# SCH.net
KiCad netlist of a schematic drawn in EasyEDA
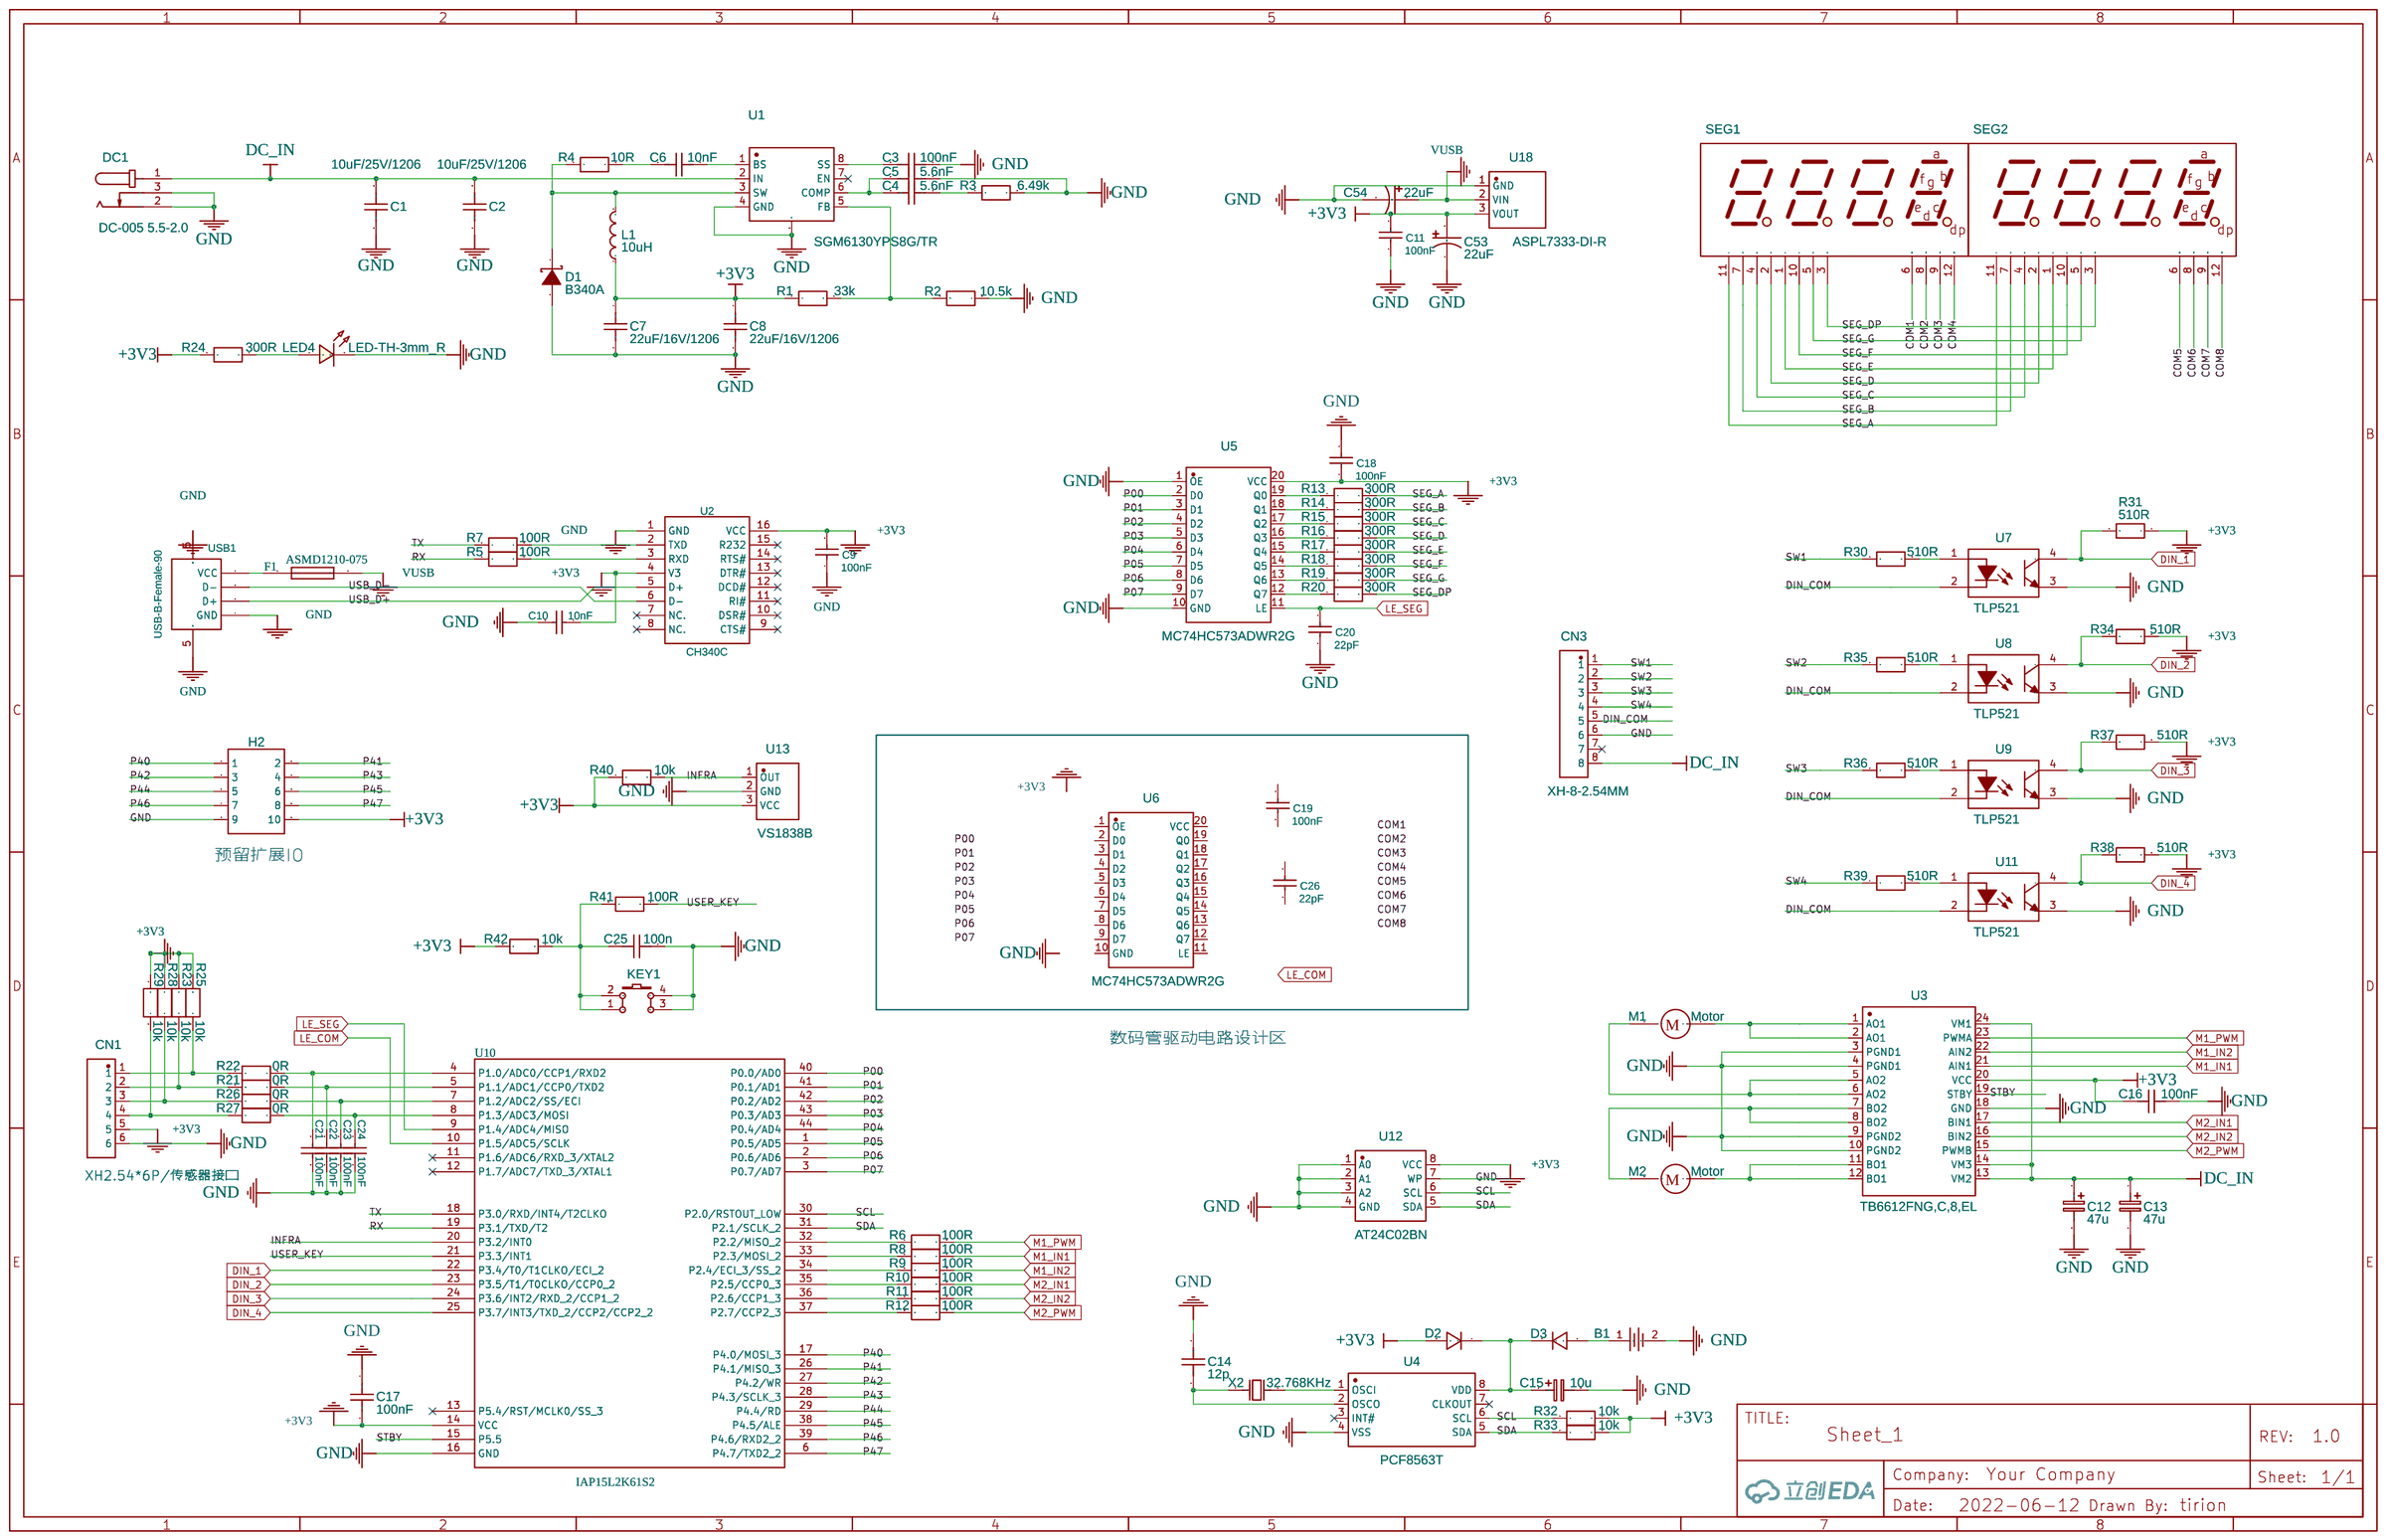
[diagram p0: schematic sheet]

(export (version "E")
  (design (tool "Eeschema 10.0.6"))
  (components
    (comp (ref "B1")
      (value "CR1220-2")
      (fields (field (name "BOM_Supplier Part") "C70381"))
      (libsource (lib "") (part "CR1220-2"))
    )
    (comp (ref "C1") (value "10uF/25V/1206") (libsource (lib "") (part "C_1206_US")))
    (comp (ref "C2") (value "10uF/25V/1206") (libsource (lib "") (part "C_1206_US")))
    (comp (ref "C3") (value "100nF") (libsource (lib "") (part "C_0805_US")))
    (comp (ref "C4") (value "5.6nF") (libsource (lib "") (part "C_0805_US")))
    (comp (ref "C5") (value "5.6nF") (libsource (lib "") (part "C_0805_US")))
    (comp (ref "C6") (value "10nF") (libsource (lib "") (part "C_0805_US")))
    (comp (ref "C7") (value "22uF/16V/1206") (libsource (lib "") (part "C_0805_US_2")))
    (comp (ref "C8") (value "22uF/16V/1206") (libsource (lib "") (part "C_0805_US_2")))
    (comp (ref "C9")
      (value "100nF")
      (fields
        (field (name "BOM_Manufacturer Part") "0805F104M500NT")
        (field (name "BOM_Supplier Part") "C28378")
      )
      (libsource (lib "") (part "0805F104M500NT_1"))
    )
    (comp (ref "C10")
      (value "10nF")
      (fields
        (field (name "BOM_Manufacturer Part") "0805F104M500NT")
        (field (name "BOM_Supplier Part") "C28378")
      )
      (libsource (lib "") (part "0805F104M500NT_2"))
    )
    (comp (ref "C11")
      (value "100nF")
      (fields
        (field (name "BOM_Manufacturer Part") "0805F104M500NT")
        (field (name "BOM_Supplier Part") "C28378")
      )
      (libsource (lib "") (part "0805F104M500NT_1"))
    )
    (comp (ref "C12") (value "47u") (libsource (lib "") (part "CE_SMD_D6.3×H5.5_EU")))
    (comp (ref "C13") (value "47u") (libsource (lib "") (part "CE_SMD_D6.3×H5.5_EU")))
    (comp (ref "C14") (value "12p") (libsource (lib "") (part "C_0805_US_2")))
    (comp (ref "C15") (value "10u") (libsource (lib "") (part "CE_SMD_D5.0×H5.5_EU")))
    (comp (ref "C16") (value "100nF") (libsource (lib "") (part "C_0805_US_1")))
    (comp (ref "C17") (value "100nF") (libsource (lib "") (part "C_0805_US_2")))
    (comp (ref "C18")
      (value "100nF")
      (fields
        (field (name "BOM_Manufacturer Part") "0805F104M500NT")
        (field (name "BOM_Supplier Part") "C28378")
      )
      (libsource (lib "") (part "0805F104M500NT_1"))
    )
    (comp (ref "C19")
      (value "100nF")
      (fields
        (field (name "BOM_Manufacturer Part") "0805F104M500NT")
        (field (name "BOM_Supplier Part") "C28378")
      )
      (libsource (lib "") (part "0805F104M500NT_1"))
    )
    (comp (ref "C20")
      (value "22pF")
      (fields
        (field (name "BOM_Manufacturer Part") "0805F104M500NT")
        (field (name "BOM_Supplier Part") "C28378")
      )
      (libsource (lib "") (part "0805F104M500NT_1"))
    )
    (comp (ref "C21")
      (value "100nF")
      (fields
        (field (name "BOM_Manufacturer Part") "0805F104M500NT")
        (field (name "BOM_Supplier Part") "C28378")
      )
      (libsource (lib "") (part "0805F104M500NT"))
    )
    (comp (ref "C22")
      (value "100nF")
      (fields
        (field (name "BOM_Manufacturer Part") "0805F104M500NT")
        (field (name "BOM_Supplier Part") "C28378")
      )
      (libsource (lib "") (part "0805F104M500NT"))
    )
    (comp (ref "C23")
      (value "100nF")
      (fields
        (field (name "BOM_Manufacturer Part") "0805F104M500NT")
        (field (name "BOM_Supplier Part") "C28378")
      )
      (libsource (lib "") (part "0805F104M500NT"))
    )
    (comp (ref "C24")
      (value "100nF")
      (fields
        (field (name "BOM_Manufacturer Part") "0805F104M500NT")
        (field (name "BOM_Supplier Part") "C28378")
      )
      (libsource (lib "") (part "0805F104M500NT"))
    )
    (comp (ref "C25") (value "100n") (libsource (lib "") (part "C_0805_US_1")))
    (comp (ref "C26")
      (value "22pF")
      (fields
        (field (name "BOM_Manufacturer Part") "0805F104M500NT")
        (field (name "BOM_Supplier Part") "C28378")
      )
      (libsource (lib "") (part "0805F104M500NT_1"))
    )
    (comp (ref "C53")
      (value "22uF")
      (fields (field (name "BOM_Supplier Part") "C27783"))
      (libsource (lib "") (part "CAP-50V22UF"))
    )
    (comp (ref "C54")
      (value "22uF")
      (fields (field (name "BOM_Supplier Part") "C27783"))
      (libsource (lib "") (part "CAP-50V22UF_1"))
    )
    (comp (ref "CN1")
      (value "XH2.54*6P/传感器接口")
      (fields
        (field (name "BOM_Manufacturer Part") "XH2.54*6P_直插")
        (field (name "BOM_Supplier Part") "C9900008614")
      )
      (libsource (lib "") (part "XH2.54*6P_直插"))
    )
    (comp (ref "CN3")
      (value "XH-8-2.54MM")
      (fields (field (name "BOM_Supplier Part") "C9900005540"))
      (libsource (lib "") (part "XH-8-2.54MM"))
    )
    (comp (ref "D1")
      (value "B340A")
      (fields (field (name "BOM_Supplier Part") "C64982"))
      (libsource (lib "") (part "B340A"))
    )
    (comp (ref "D2")
      (value "1N4148")
      (fields (field (name "BOM_Supplier Part") "C13769"))
      (libsource (lib "") (part "1N4148"))
    )
    (comp (ref "D3")
      (value "1N4148")
      (fields (field (name "BOM_Supplier Part") "C13769"))
      (libsource (lib "") (part "1N4148_1"))
    )
    (comp (ref "DC1")
      (value "DC-005 5.5-2.0")
      (fields (field (name "BOM_Supplier Part") "C132516"))
      (libsource (lib "") (part "dc-005 5.5-2.0"))
    )
    (comp (ref "F1") (value "ASMD1210-075") (libsource (lib "") (part "Unknown_200_-690")))
    (comp (ref "H2")
      (value "HDR-F-2.54_2x5")
      (fields (field (name "BOM_Supplier Part") "C30419"))
      (libsource (lib "") (part "HDR-F-2.54_2x5"))
    )
    (comp (ref "KEY1")
      (value "K4-6×6_SMD")
      (fields
        (field (name "BOM_Manufacturer Part") "K2-6639SP-D4SC-04")
        (field (name "BOM_Supplier Part") "C191626")
      )
      (libsource (lib "") (part "K4-6×6_SMD"))
    )
    (comp (ref "L1")
      (value "10uH")
      (fields
        (field (name "BOM_Manufacturer Part") "1217AS-H-100M=P3")
        (field (name "BOM_Supplier Part") "C237597")
      )
      (libsource (lib "") (part "1217AS-H-100M=P3"))
    )
    (comp (ref "LED4")
      (value "LED-TH-3mm_R")
      (fields
        (field (name "BOM_Manufacturer Part") "204-10SDRD/S530-A3-L")
        (field (name "BOM_Supplier Part") "C84774")
      )
      (libsource (lib "") (part "LED-TH-3mm_R"))
    )
    (comp (ref "M1") (value "Motor") (libsource (lib "") (part "Motor")))
    (comp (ref "M2") (value "Motor") (libsource (lib "") (part "Motor")))
    (comp (ref "R1") (value "33k") (libsource (lib "") (part "R_0805_EU")))
    (comp (ref "R2") (value "10.5k") (libsource (lib "") (part "R_0805_EU_2")))
    (comp (ref "R3") (value "6.49k") (libsource (lib "") (part "R_0805_EU")))
    (comp (ref "R4") (value "10R") (libsource (lib "") (part "R_0805_EU")))
    (comp (ref "R5") (value "100R") (libsource (lib "") (part "R_0805_EU")))
    (comp (ref "R6") (value "100R") (libsource (lib "") (part "R_0805_EU")))
    (comp (ref "R7") (value "100R") (libsource (lib "") (part "R_0805_EU")))
    (comp (ref "R8") (value "100R") (libsource (lib "") (part "R_0805_EU")))
    (comp (ref "R9") (value "100R") (libsource (lib "") (part "R_0805_EU")))
    (comp (ref "R10") (value "100R") (libsource (lib "") (part "R_0805_EU")))
    (comp (ref "R11") (value "100R") (libsource (lib "") (part "R_0805_EU")))
    (comp (ref "R12") (value "100R") (libsource (lib "") (part "R_0805_EU")))
    (comp (ref "R13") (value "300R") (libsource (lib "") (part "R_0805_EU")))
    (comp (ref "R14") (value "300R") (libsource (lib "") (part "R_0805_EU")))
    (comp (ref "R15") (value "300R") (libsource (lib "") (part "R_0805_EU")))
    (comp (ref "R16") (value "300R") (libsource (lib "") (part "R_0805_EU")))
    (comp (ref "R17") (value "300R") (libsource (lib "") (part "R_0805_EU")))
    (comp (ref "R18") (value "300R") (libsource (lib "") (part "R_0805_EU")))
    (comp (ref "R19") (value "300R") (libsource (lib "") (part "R_0805_EU")))
    (comp (ref "R20") (value "300R") (libsource (lib "") (part "R_0805_EU")))
    (comp (ref "R21") (value "0R") (libsource (lib "") (part "R_0805_EU")))
    (comp (ref "R22") (value "0R") (libsource (lib "") (part "R_0805_EU")))
    (comp (ref "R23") (value "10k") (libsource (lib "") (part "R_0805_EU_1")))
    (comp (ref "R24") (value "300R") (libsource (lib "") (part "R_0805_EU_2")))
    (comp (ref "R25") (value "10k") (libsource (lib "") (part "R_0805_EU_1")))
    (comp (ref "R26") (value "0R") (libsource (lib "") (part "R_0805_EU")))
    (comp (ref "R27") (value "0R") (libsource (lib "") (part "R_0805_EU")))
    (comp (ref "R28") (value "10k") (libsource (lib "") (part "R_0805_EU_1")))
    (comp (ref "R29") (value "10k") (libsource (lib "") (part "R_0805_EU_1")))
    (comp (ref "R30") (value "510R") (libsource (lib "") (part "R_0805_EU")))
    (comp (ref "R31") (value "510R") (libsource (lib "") (part "R_0805_EU_2")))
    (comp (ref "R32") (value "10k") (libsource (lib "") (part "R_0805_EU")))
    (comp (ref "R33") (value "10k") (libsource (lib "") (part "R_0805_EU")))
    (comp (ref "R34") (value "510R") (libsource (lib "") (part "R_0805_EU_2")))
    (comp (ref "R35") (value "510R") (libsource (lib "") (part "R_0805_EU")))
    (comp (ref "R36") (value "510R") (libsource (lib "") (part "R_0805_EU")))
    (comp (ref "R37") (value "510R") (libsource (lib "") (part "R_0805_EU_2")))
    (comp (ref "R38") (value "510R") (libsource (lib "") (part "R_0805_EU_2")))
    (comp (ref "R39") (value "510R") (libsource (lib "") (part "R_0805_EU")))
    (comp (ref "R40") (value "10k") (libsource (lib "") (part "R_0805_EU")))
    (comp (ref "R41") (value "100R") (libsource (lib "") (part "R_0805_EU_2")))
    (comp (ref "R42") (value "10k") (libsource (lib "") (part "R_0805_EU_2")))
    (comp (ref "SEG1")
      (value "0.36寸4位数码管")
      (fields
        (field (name "BOM_Manufacturer Part") "FJ5461BH 纯红")
        (field (name "BOM_Supplier Part") "C38183")
      )
      (libsource (lib "") (part "0.36寸4位数码管"))
    )
    (comp (ref "SEG2")
      (value "0.36寸4位数码管")
      (fields
        (field (name "BOM_Manufacturer Part") "FJ5461BH 纯红")
        (field (name "BOM_Supplier Part") "C38183")
      )
      (libsource (lib "") (part "0.36寸4位数码管"))
    )
    (comp (ref "U1")
      (value "SGM6130YPS8G/TR")
      (fields (field (name "BOM_Supplier Part") "C87094"))
      (libsource (lib "") (part "SGM6130YPS8G/TR"))
    )
    (comp (ref "U2")
      (value "CH340C")
      (fields (field (name "BOM_Supplier Part") "C84681"))
      (libsource (lib "") (part "CH340C"))
    )
    (comp (ref "U3")
      (value "TB6612FNG,C,8,EL")
      (fields (field (name "BOM_Supplier Part") "C141517"))
      (libsource (lib "") (part "TB6612FNG,C,8,EL"))
    )
    (comp (ref "U4")
      (value "PCF8563T")
      (fields
        (field (name "BOM_Manufacturer Part") "PCF8563T/5,518")
        (field (name "BOM_Supplier Part") "C7440")
      )
      (libsource (lib "") (part "PCF8563T/5,518"))
    )
    (comp (ref "U5")
      (value "MC74HC573ADWR2G")
      (fields (field (name "BOM_Supplier Part") "C233618"))
      (libsource (lib "") (part "MC74HC573ADWR2G"))
    )
    (comp (ref "U6")
      (value "MC74HC573ADWR2G")
      (fields (field (name "BOM_Supplier Part") "C233618"))
      (libsource (lib "") (part "MC74HC573ADWR2G"))
    )
    (comp (ref "U7")
      (value "TLP521")
      (fields (field (name "BOM_Supplier Part") "C9900005355"))
      (libsource (lib "") (part "TLP521"))
    )
    (comp (ref "U8")
      (value "TLP521")
      (fields (field (name "BOM_Supplier Part") "C9900005355"))
      (libsource (lib "") (part "TLP521"))
    )
    (comp (ref "U9")
      (value "TLP521")
      (fields (field (name "BOM_Supplier Part") "C9900005355"))
      (libsource (lib "") (part "TLP521"))
    )
    (comp (ref "U10") (value "IAP15L2K61S2") (libsource (lib "") (part "Unknown_330_-335")))
    (comp (ref "U11")
      (value "TLP521")
      (fields (field (name "BOM_Supplier Part") "C9900005355"))
      (libsource (lib "") (part "TLP521"))
    )
    (comp (ref "U12")
      (value "AT24C02BN")
      (fields (field (name "BOM_Supplier Part") "C9900013198"))
      (libsource (lib "") (part "AT24C02BN"))
    )
    (comp (ref "U13")
      (value "VS1838B")
      (fields (field (name "BOM_Supplier Part") "C9900002107"))
      (libsource (lib "") (part "VS1838B"))
    )
    (comp (ref "U18")
      (value "ASPL7333-DI-R")
      (fields (field (name "BOM_Supplier Part") "C2758205"))
      (libsource (lib "") (part "ASPL7333-DI-R"))
    )
    (comp (ref "USB1")
      (value "USB-B-Female-90")
      (fields (field (name "BOM_Manufacturer Part") "USB-BF90") (field (name "BOM_Supplier Part") "C46392"))
      (libsource (lib "") (part "USB-B-Female-90"))
    )
    (comp (ref "X2")
      (value "32.768KHz")
      (fields
        (field (name "BOM_Manufacturer Part") "6K832768F12UB")
        (field (name "BOM_Supplier Part") "C252404")
      )
      (libsource (lib "") (part "6K832768F12UB"))
    )
  )
  (nets
    (net (code "1") (name "+3V3") (class "Default")
      (node (ref "C10") (pin "1") (pinfunction "1_1") (pintype "unspecified"))
      (node (ref "C11") (pin "2") (pinfunction "2_2") (pintype "unspecified"))
      (node (ref "C16") (pin "1") (pinfunction "1_1") (pintype "unspecified"))
      (node (ref "C17") (pin "2") (pinfunction "2_2") (pintype "unspecified"))
      (node (ref "C18") (pin "1") (pinfunction "1_1") (pintype "unspecified"))
      (node (ref "C53") (pin "1") (pinfunction "1_1") (pintype "unspecified"))
      (node (ref "C7") (pin "1") (pinfunction "1_1") (pintype "unspecified"))
      (node (ref "C8") (pin "1") (pinfunction "1_1") (pintype "unspecified"))
      (node (ref "C9") (pin "2") (pinfunction "2_2") (pintype "unspecified"))
      (node (ref "CN1") (pin "5") (pinfunction "5_5") (pintype "unspecified"))
      (node (ref "D2") (pin "2") (pinfunction "2_2") (pintype "unspecified"))
      (node (ref "H2") (pin "10") (pinfunction "10_10") (pintype "unspecified"))
      (node (ref "L1") (pin "1") (pinfunction "1_1") (pintype "unspecified"))
      (node (ref "R1") (pin "1") (pinfunction "1_1") (pintype "unspecified"))
      (node (ref "R23") (pin "1") (pinfunction "1_1") (pintype "unspecified"))
      (node (ref "R24") (pin "2") (pinfunction "2_2") (pintype "unspecified"))
      (node (ref "R25") (pin "1") (pinfunction "1_1") (pintype "unspecified"))
      (node (ref "R28") (pin "1") (pinfunction "1_1") (pintype "unspecified"))
      (node (ref "R29") (pin "1") (pinfunction "1_1") (pintype "unspecified"))
      (node (ref "R31") (pin "1") (pinfunction "1_1") (pintype "unspecified"))
      (node (ref "R32") (pin "2") (pinfunction "2_2") (pintype "unspecified"))
      (node (ref "R33") (pin "2") (pinfunction "2_2") (pintype "unspecified"))
      (node (ref "R34") (pin "1") (pinfunction "1_1") (pintype "unspecified"))
      (node (ref "R37") (pin "1") (pinfunction "1_1") (pintype "unspecified"))
      (node (ref "R38") (pin "1") (pinfunction "1_1") (pintype "unspecified"))
      (node (ref "R40") (pin "1") (pinfunction "1_1") (pintype "unspecified"))
      (node (ref "R42") (pin "2") (pinfunction "2_2") (pintype "unspecified"))
      (node (ref "U10") (pin "14") (pinfunction "VCC_14") (pintype "passive"))
      (node (ref "U12") (pin "8") (pinfunction "VCC_8") (pintype "unspecified"))
      (node (ref "U13") (pin "3") (pinfunction "VCC_3") (pintype "unspecified"))
      (node (ref "U18") (pin "3") (pinfunction "VOUT_3") (pintype "unspecified"))
      (node (ref "U2") (pin "16") (pinfunction "VCC_16") (pintype "unspecified"))
      (node (ref "U2") (pin "4") (pinfunction "V3_4") (pintype "unspecified"))
      (node (ref "U3") (pin "20") (pinfunction "VCC_20") (pintype "unspecified"))
      (node (ref "U5") (pin "20") (pinfunction "VCC_20") (pintype "unspecified"))
    )
    (net (code "2") (name "/COM1") (class "Default")
      (node (ref "SEG1") (pin "6") (pinfunction "DIG4_6") (pintype "input"))
    )
    (net (code "3") (name "/COM2") (class "Default")
      (node (ref "SEG1") (pin "8") (pinfunction "DIG3_8") (pintype "input"))
    )
    (net (code "4") (name "/COM3") (class "Default")
      (node (ref "SEG1") (pin "9") (pinfunction "DIG2_9") (pintype "input"))
    )
    (net (code "5") (name "/COM4") (class "Default")
      (node (ref "SEG1") (pin "12") (pinfunction "DIG1_12") (pintype "input"))
    )
    (net (code "6") (name "/COM5") (class "Default")
      (node (ref "SEG2") (pin "6") (pinfunction "DIG4_6") (pintype "input"))
    )
    (net (code "7") (name "/COM6") (class "Default")
      (node (ref "SEG2") (pin "8") (pinfunction "DIG3_8") (pintype "input"))
    )
    (net (code "8") (name "/COM7") (class "Default")
      (node (ref "SEG2") (pin "9") (pinfunction "DIG2_9") (pintype "input"))
    )
    (net (code "9") (name "/COM8") (class "Default")
      (node (ref "SEG2") (pin "12") (pinfunction "DIG1_12") (pintype "input"))
    )
    (net (code "10") (name "/DIN_COM") (class "Default")
      (node (ref "CN3") (pin "5") (pinfunction "5_5") (pintype "unspecified"))
      (node (ref "U11") (pin "2") (pinfunction "2_2") (pintype "unspecified"))
      (node (ref "U7") (pin "2") (pinfunction "2_2") (pintype "unspecified"))
      (node (ref "U8") (pin "2") (pinfunction "2_2") (pintype "unspecified"))
      (node (ref "U9") (pin "2") (pinfunction "2_2") (pintype "unspecified"))
    )
    (net (code "11") (name "/INFRA") (class "Default")
      (node (ref "R40") (pin "2") (pinfunction "2_2") (pintype "unspecified"))
      (node (ref "U10") (pin "20") (pinfunction "P3.2/INT0_20") (pintype "unspecified"))
      (node (ref "U13") (pin "1") (pinfunction "OUT_1") (pintype "unspecified"))
    )
    (net (code "12") (name "/P00") (class "Default")
      (node (ref "U10") (pin "40") (pinfunction "P0.0/AD0_40") (pintype "bidirectional"))
      (node (ref "U5") (pin "2") (pinfunction "D0_2") (pintype "unspecified"))
    )
    (net (code "13") (name "/P01") (class "Default")
      (node (ref "U10") (pin "41") (pinfunction "P0.1/AD1_41") (pintype "bidirectional"))
      (node (ref "U5") (pin "3") (pinfunction "D1_3") (pintype "unspecified"))
    )
    (net (code "14") (name "/P02") (class "Default")
      (node (ref "U10") (pin "42") (pinfunction "P0.2/AD2_42") (pintype "bidirectional"))
      (node (ref "U5") (pin "4") (pinfunction "D2_4") (pintype "unspecified"))
    )
    (net (code "15") (name "/P03") (class "Default")
      (node (ref "U10") (pin "43") (pinfunction "P0.3/AD3_43") (pintype "bidirectional"))
      (node (ref "U5") (pin "5") (pinfunction "D3_5") (pintype "unspecified"))
    )
    (net (code "16") (name "/P04") (class "Default")
      (node (ref "U10") (pin "44") (pinfunction "P0.4/AD4_44") (pintype "bidirectional"))
      (node (ref "U5") (pin "6") (pinfunction "D4_6") (pintype "unspecified"))
    )
    (net (code "17") (name "/P05") (class "Default")
      (node (ref "U10") (pin "1") (pinfunction "P0.5/AD5_1") (pintype "bidirectional"))
      (node (ref "U5") (pin "7") (pinfunction "D5_7") (pintype "unspecified"))
    )
    (net (code "18") (name "/P06") (class "Default")
      (node (ref "U10") (pin "2") (pinfunction "P0.6/AD6_2") (pintype "bidirectional"))
      (node (ref "U5") (pin "8") (pinfunction "D6_8") (pintype "unspecified"))
    )
    (net (code "19") (name "/P07") (class "Default")
      (node (ref "U10") (pin "3") (pinfunction "P0.7/AD7_3") (pintype "bidirectional"))
      (node (ref "U5") (pin "9") (pinfunction "D7_9") (pintype "unspecified"))
    )
    (net (code "20") (name "/P40") (class "Default")
      (node (ref "H2") (pin "1") (pinfunction "1_1") (pintype "unspecified"))
      (node (ref "U10") (pin "17") (pinfunction "P4.0/MOSI_3_17") (pintype "bidirectional"))
    )
    (net (code "21") (name "/P41") (class "Default")
      (node (ref "H2") (pin "2") (pinfunction "2_2") (pintype "unspecified"))
      (node (ref "U10") (pin "26") (pinfunction "P4.1/MISO_3_26") (pintype "bidirectional"))
    )
    (net (code "22") (name "/P42") (class "Default")
      (node (ref "H2") (pin "3") (pinfunction "3_3") (pintype "unspecified"))
      (node (ref "U10") (pin "27") (pinfunction "P4.2/WR_27") (pintype "unspecified"))
    )
    (net (code "23") (name "/P43") (class "Default")
      (node (ref "H2") (pin "4") (pinfunction "4_4") (pintype "unspecified"))
      (node (ref "U10") (pin "28") (pinfunction "P4.3/SCLK_3_28") (pintype "bidirectional"))
    )
    (net (code "24") (name "/P44") (class "Default")
      (node (ref "H2") (pin "5") (pinfunction "5_5") (pintype "unspecified"))
      (node (ref "U10") (pin "29") (pinfunction "P4.4/RD_29") (pintype "unspecified"))
    )
    (net (code "25") (name "/P45") (class "Default")
      (node (ref "H2") (pin "6") (pinfunction "6_6") (pintype "unspecified"))
      (node (ref "U10") (pin "38") (pinfunction "P4.5/ALE_38") (pintype "unspecified"))
    )
    (net (code "26") (name "/P46") (class "Default")
      (node (ref "H2") (pin "7") (pinfunction "7_7") (pintype "unspecified"))
      (node (ref "U10") (pin "39") (pinfunction "P4.6/RXD2_2_39") (pintype "unspecified"))
    )
    (net (code "27") (name "/P47") (class "Default")
      (node (ref "H2") (pin "8") (pinfunction "8_8") (pintype "unspecified"))
      (node (ref "U10") (pin "6") (pinfunction "P4.7/TXD2_2_6") (pintype "bidirectional"))
    )
    (net (code "28") (name "/RX") (class "Default")
      (node (ref "R5") (pin "1") (pinfunction "1_1") (pintype "unspecified"))
      (node (ref "U10") (pin "19") (pinfunction "P3.1/TXD/T2_19") (pintype "unspecified"))
    )
    (net (code "29") (name "/SCL") (class "Default")
      (node (ref "R32") (pin "1") (pinfunction "1_1") (pintype "unspecified"))
      (node (ref "U10") (pin "30") (pinfunction "P2.0/RSTOUT_LOW_30") (pintype "bidirectional"))
      (node (ref "U12") (pin "6") (pinfunction "SCL_6") (pintype "unspecified"))
      (node (ref "U4") (pin "6") (pinfunction "SCL_6") (pintype "unspecified"))
    )
    (net (code "30") (name "/SDA") (class "Default")
      (node (ref "R33") (pin "1") (pinfunction "1_1") (pintype "unspecified"))
      (node (ref "U10") (pin "31") (pinfunction "P2.1/SCLK_2_31") (pintype "bidirectional"))
      (node (ref "U12") (pin "5") (pinfunction "SDA_5") (pintype "unspecified"))
      (node (ref "U4") (pin "5") (pinfunction "SDA_5") (pintype "unspecified"))
    )
    (net (code "31") (name "/SEG_A") (class "Default")
      (node (ref "R13") (pin "2") (pinfunction "2_2") (pintype "unspecified"))
      (node (ref "SEG1") (pin "11") (pinfunction "A_11") (pintype "input"))
      (node (ref "SEG2") (pin "11") (pinfunction "A_11") (pintype "input"))
    )
    (net (code "32") (name "/SEG_B") (class "Default")
      (node (ref "R14") (pin "2") (pinfunction "2_2") (pintype "unspecified"))
      (node (ref "SEG1") (pin "7") (pinfunction "B_7") (pintype "input"))
      (node (ref "SEG2") (pin "7") (pinfunction "B_7") (pintype "input"))
    )
    (net (code "33") (name "/SEG_C") (class "Default")
      (node (ref "R15") (pin "2") (pinfunction "2_2") (pintype "unspecified"))
      (node (ref "SEG1") (pin "4") (pinfunction "C_4") (pintype "input"))
      (node (ref "SEG2") (pin "4") (pinfunction "C_4") (pintype "input"))
    )
    (net (code "34") (name "/SEG_D") (class "Default")
      (node (ref "R16") (pin "2") (pinfunction "2_2") (pintype "unspecified"))
      (node (ref "SEG1") (pin "2") (pinfunction "D_2") (pintype "input"))
      (node (ref "SEG2") (pin "2") (pinfunction "D_2") (pintype "input"))
    )
    (net (code "35") (name "/SEG_DP") (class "Default")
      (node (ref "R20") (pin "2") (pinfunction "2_2") (pintype "unspecified"))
      (node (ref "SEG1") (pin "3") (pinfunction "DP_3") (pintype "input"))
      (node (ref "SEG2") (pin "3") (pinfunction "DP_3") (pintype "input"))
    )
    (net (code "36") (name "/SEG_E") (class "Default")
      (node (ref "R17") (pin "2") (pinfunction "2_2") (pintype "unspecified"))
      (node (ref "SEG1") (pin "1") (pinfunction "E_1") (pintype "input"))
      (node (ref "SEG2") (pin "1") (pinfunction "E_1") (pintype "input"))
    )
    (net (code "37") (name "/SEG_F") (class "Default")
      (node (ref "R18") (pin "2") (pinfunction "2_2") (pintype "unspecified"))
      (node (ref "SEG1") (pin "10") (pinfunction "F_10") (pintype "input"))
      (node (ref "SEG2") (pin "10") (pinfunction "F_10") (pintype "input"))
    )
    (net (code "38") (name "/SEG_G") (class "Default")
      (node (ref "R19") (pin "2") (pinfunction "2_2") (pintype "unspecified"))
      (node (ref "SEG1") (pin "5") (pinfunction "G_5") (pintype "input"))
      (node (ref "SEG2") (pin "5") (pinfunction "G_5") (pintype "input"))
    )
    (net (code "39") (name "/STBY") (class "Default")
      (node (ref "U10") (pin "15") (pinfunction "P5.5_15") (pintype "unspecified"))
      (node (ref "U3") (pin "19") (pinfunction "STBY_19") (pintype "unspecified"))
    )
    (net (code "40") (name "/SW1") (class "Default")
      (node (ref "CN3") (pin "1") (pinfunction "1_1") (pintype "unspecified"))
      (node (ref "R30") (pin "1") (pinfunction "1_1") (pintype "unspecified"))
    )
    (net (code "41") (name "/SW2") (class "Default")
      (node (ref "CN3") (pin "2") (pinfunction "2_2") (pintype "unspecified"))
      (node (ref "R35") (pin "1") (pinfunction "1_1") (pintype "unspecified"))
    )
    (net (code "42") (name "/SW3") (class "Default")
      (node (ref "CN3") (pin "3") (pinfunction "3_3") (pintype "unspecified"))
      (node (ref "R36") (pin "1") (pinfunction "1_1") (pintype "unspecified"))
    )
    (net (code "43") (name "/SW4") (class "Default")
      (node (ref "CN3") (pin "4") (pinfunction "4_4") (pintype "unspecified"))
      (node (ref "R39") (pin "1") (pinfunction "1_1") (pintype "unspecified"))
    )
    (net (code "44") (name "/TX") (class "Default")
      (node (ref "R7") (pin "1") (pinfunction "1_1") (pintype "unspecified"))
      (node (ref "U10") (pin "18") (pinfunction "P3.0/RXD/INT4/T2CLKO_18") (pintype "unspecified"))
    )
    (net (code "45") (name "/USB_D+") (class "Default")
      (node (ref "U2") (pin "5") (pinfunction "D+_5") (pintype "unspecified"))
      (node (ref "USB1") (pin "3") (pinfunction "D+_3") (pintype "unspecified"))
    )
    (net (code "46") (name "/USB_D-") (class "Default")
      (node (ref "U2") (pin "6") (pinfunction "D-_6") (pintype "unspecified"))
      (node (ref "USB1") (pin "2") (pinfunction "D-_2") (pintype "unspecified"))
    )
    (net (code "47") (name "/USER_KEY") (class "Default")
      (node (ref "R41") (pin "1") (pinfunction "1_1") (pintype "unspecified"))
      (node (ref "U10") (pin "21") (pinfunction "P3.3/INT1_21") (pintype "unspecified"))
    )
    (net (code "48") (name "DC_IN") (class "Default")
      (node (ref "C1") (pin "2") (pinfunction "2_2") (pintype "unspecified"))
      (node (ref "C12") (pin "1") (pinfunction "1_1") (pintype "unspecified"))
      (node (ref "C13") (pin "1") (pinfunction "1_1") (pintype "unspecified"))
      (node (ref "C2") (pin "2") (pinfunction "2_2") (pintype "unspecified"))
      (node (ref "CN3") (pin "8") (pinfunction "8_8") (pintype "unspecified"))
      (node (ref "DC1") (pin "1") (pinfunction "1_1") (pintype "unspecified"))
      (node (ref "U1") (pin "2") (pinfunction "IN_2") (pintype "unspecified"))
      (node (ref "U3") (pin "13") (pinfunction "VM2_13") (pintype "unspecified"))
      (node (ref "U3") (pin "14") (pinfunction "VM3_14") (pintype "unspecified"))
      (node (ref "U3") (pin "24") (pinfunction "VM1_24") (pintype "unspecified"))
    )
    (net (code "49") (name "DIN_1") (class "Default")
      (node (ref "R31") (pin "2") (pinfunction "2_2") (pintype "unspecified"))
      (node (ref "U10") (pin "22") (pinfunction "P3.4/T0/T1CLKO/ECI_2_22") (pintype "bidirectional"))
      (node (ref "U7") (pin "4") (pinfunction "4_4") (pintype "unspecified"))
    )
    (net (code "50") (name "DIN_2") (class "Default")
      (node (ref "R34") (pin "2") (pinfunction "2_2") (pintype "unspecified"))
      (node (ref "U10") (pin "23") (pinfunction "P3.5/T1/T0CLKO/CCP0_2_23") (pintype "unspecified"))
      (node (ref "U8") (pin "4") (pinfunction "4_4") (pintype "unspecified"))
    )
    (net (code "51") (name "DIN_3") (class "Default")
      (node (ref "R37") (pin "2") (pinfunction "2_2") (pintype "unspecified"))
      (node (ref "U10") (pin "24") (pinfunction "P3.6/INT2/RXD_2/CCP1_2_24") (pintype "unspecified"))
      (node (ref "U9") (pin "4") (pinfunction "4_4") (pintype "unspecified"))
    )
    (net (code "52") (name "DIN_4") (class "Default")
      (node (ref "R38") (pin "2") (pinfunction "2_2") (pintype "unspecified"))
      (node (ref "U10") (pin "25") (pinfunction "P3.7/INT3/TXD_2/CCP2/CCP2_2_25") (pintype "unspecified"))
      (node (ref "U11") (pin "4") (pinfunction "4_4") (pintype "unspecified"))
    )
    (net (code "53") (name "GND") (class "Default")
      (node (ref "B1") (pin "2") (pinfunction "2_2") (pintype "input"))
      (node (ref "C1") (pin "1") (pinfunction "1_1") (pintype "unspecified"))
      (node (ref "C10") (pin "2") (pinfunction "2_2") (pintype "unspecified"))
      (node (ref "C11") (pin "1") (pinfunction "1_1") (pintype "unspecified"))
      (node (ref "C12") (pin "2") (pinfunction "2_2") (pintype "unspecified"))
      (node (ref "C13") (pin "2") (pinfunction "2_2") (pintype "unspecified"))
      (node (ref "C14") (pin "1") (pinfunction "1_1") (pintype "unspecified"))
      (node (ref "C15") (pin "2") (pinfunction "2_2") (pintype "unspecified"))
      (node (ref "C16") (pin "2") (pinfunction "2_2") (pintype "unspecified"))
      (node (ref "C17") (pin "1") (pinfunction "1_1") (pintype "unspecified"))
      (node (ref "C18") (pin "2") (pinfunction "2_2") (pintype "unspecified"))
      (node (ref "C2") (pin "1") (pinfunction "1_1") (pintype "unspecified"))
      (node (ref "C20") (pin "1") (pinfunction "1_1") (pintype "unspecified"))
      (node (ref "C21") (pin "2") (pinfunction "2_2") (pintype "unspecified"))
      (node (ref "C22") (pin "2") (pinfunction "2_2") (pintype "unspecified"))
      (node (ref "C23") (pin "2") (pinfunction "2_2") (pintype "unspecified"))
      (node (ref "C24") (pin "2") (pinfunction "2_2") (pintype "unspecified"))
      (node (ref "C25") (pin "2") (pinfunction "2_2") (pintype "unspecified"))
      (node (ref "C3") (pin "1") (pinfunction "1_1") (pintype "unspecified"))
      (node (ref "C5") (pin "1") (pinfunction "1_1") (pintype "unspecified"))
      (node (ref "C53") (pin "2") (pinfunction "2_2") (pintype "unspecified"))
      (node (ref "C54") (pin "2") (pinfunction "2_2") (pintype "unspecified"))
      (node (ref "C7") (pin "2") (pinfunction "2_2") (pintype "unspecified"))
      (node (ref "C8") (pin "2") (pinfunction "2_2") (pintype "unspecified"))
      (node (ref "C9") (pin "1") (pinfunction "1_1") (pintype "unspecified"))
      (node (ref "CN1") (pin "6") (pinfunction "6_6") (pintype "unspecified"))
      (node (ref "CN3") (pin "6") (pinfunction "6_6") (pintype "unspecified"))
      (node (ref "D1") (pin "2") (pinfunction "A_2") (pintype "unspecified"))
      (node (ref "DC1") (pin "2") (pinfunction "2_2") (pintype "unspecified"))
      (node (ref "DC1") (pin "3") (pinfunction "3_3") (pintype "unspecified"))
      (node (ref "H2") (pin "9") (pinfunction "9_9") (pintype "unspecified"))
      (node (ref "KEY1") (pin "3") (pinfunction "3_3") (pintype "unspecified"))
      (node (ref "KEY1") (pin "4") (pinfunction "4_4") (pintype "unspecified"))
      (node (ref "LED4") (pin "2") (pinfunction "2_2") (pintype "unspecified"))
      (node (ref "R2") (pin "1") (pinfunction "1_1") (pintype "unspecified"))
      (node (ref "R3") (pin "2") (pinfunction "2_2") (pintype "unspecified"))
      (node (ref "U1") (pin "4") (pinfunction "GND_4") (pintype "unspecified"))
      (node (ref "U1") (pin "9") (pinfunction "9_9") (pintype "unspecified"))
      (node (ref "U10") (pin "16") (pinfunction "GND_16") (pintype "passive"))
      (node (ref "U11") (pin "3") (pinfunction "3_3") (pintype "unspecified"))
      (node (ref "U12") (pin "1") (pinfunction "A0_1") (pintype "unspecified"))
      (node (ref "U12") (pin "2") (pinfunction "A1_2") (pintype "unspecified"))
      (node (ref "U12") (pin "3") (pinfunction "A2_3") (pintype "unspecified"))
      (node (ref "U12") (pin "4") (pinfunction "GND_4") (pintype "unspecified"))
      (node (ref "U12") (pin "7") (pinfunction "WP_7") (pintype "unspecified"))
      (node (ref "U13") (pin "2") (pinfunction "GND_2") (pintype "unspecified"))
      (node (ref "U18") (pin "1") (pinfunction "GND_1") (pintype "unspecified"))
      (node (ref "U2") (pin "1") (pinfunction "GND_1") (pintype "unspecified"))
      (node (ref "U3") (pin "10") (pinfunction "PGND2_10") (pintype "unspecified"))
      (node (ref "U3") (pin "18") (pinfunction "GND_18") (pintype "unspecified"))
      (node (ref "U3") (pin "3") (pinfunction "PGND1_3") (pintype "unspecified"))
      (node (ref "U3") (pin "4") (pinfunction "PGND1_4") (pintype "unspecified"))
      (node (ref "U3") (pin "9") (pinfunction "PGND2_9") (pintype "unspecified"))
      (node (ref "U4") (pin "4") (pinfunction "VSS_4") (pintype "unspecified"))
      (node (ref "U5") (pin "1") (pinfunction "OE_1") (pintype "unspecified"))
      (node (ref "U5") (pin "10") (pinfunction "GND_10") (pintype "unspecified"))
      (node (ref "U7") (pin "3") (pinfunction "3_3") (pintype "unspecified"))
      (node (ref "U8") (pin "3") (pinfunction "3_3") (pintype "unspecified"))
      (node (ref "U9") (pin "3") (pinfunction "3_3") (pintype "unspecified"))
      (node (ref "USB1") (pin "4") (pinfunction "GND_4") (pintype "unspecified"))
      (node (ref "USB1") (pin "5") (pinfunction "SH1_5") (pintype "unspecified"))
    )
    (net (code "54") (name "LE_COM") (class "Default")
      (node (ref "U10") (pin "10") (pinfunction "P1.5/ADC5/SCLK_10") (pintype "unspecified"))
    )
    (net (code "55") (name "LE_SEG") (class "Default")
      (node (ref "C20") (pin "2") (pinfunction "2_2") (pintype "unspecified"))
      (node (ref "U10") (pin "9") (pinfunction "P1.4/ADC4/MISO_9") (pintype "unspecified"))
      (node (ref "U5") (pin "11") (pinfunction "LE_11") (pintype "unspecified"))
    )
    (net (code "56") (name "M1_IN1") (class "Default")
      (node (ref "R8") (pin "2") (pinfunction "2_2") (pintype "unspecified"))
      (node (ref "U3") (pin "21") (pinfunction "AIN1_21") (pintype "unspecified"))
    )
    (net (code "57") (name "M1_IN2") (class "Default")
      (node (ref "R9") (pin "2") (pinfunction "2_2") (pintype "unspecified"))
      (node (ref "U3") (pin "22") (pinfunction "AIN2_22") (pintype "unspecified"))
    )
    (net (code "58") (name "M1_PWM") (class "Default")
      (node (ref "R6") (pin "2") (pinfunction "2_2") (pintype "unspecified"))
      (node (ref "U3") (pin "23") (pinfunction "PWMA_23") (pintype "unspecified"))
    )
    (net (code "59") (name "M2_IN1") (class "Default")
      (node (ref "R10") (pin "2") (pinfunction "2_2") (pintype "unspecified"))
      (node (ref "U3") (pin "17") (pinfunction "BIN1_17") (pintype "unspecified"))
    )
    (net (code "60") (name "M2_IN2") (class "Default")
      (node (ref "R11") (pin "2") (pinfunction "2_2") (pintype "unspecified"))
      (node (ref "U3") (pin "16") (pinfunction "BIN2_16") (pintype "unspecified"))
    )
    (net (code "61") (name "M2_PWM") (class "Default")
      (node (ref "R12") (pin "2") (pinfunction "2_2") (pintype "unspecified"))
      (node (ref "U3") (pin "15") (pinfunction "PWMB_15") (pintype "unspecified"))
    )
    (net (code "62") (name "Net-(B1-Pad1)") (class "Default")
      (node (ref "B1") (pin "1") (pinfunction "1_1") (pintype "input"))
      (node (ref "D3") (pin "2") (pinfunction "2_2") (pintype "unspecified"))
    )
    (net (code "63") (name "Net-(C4-Pad1)") (class "Default")
      (node (ref "C4") (pin "1") (pinfunction "1_1") (pintype "unspecified"))
      (node (ref "R3") (pin "1") (pinfunction "1_1") (pintype "unspecified"))
    )
    (net (code "64") (name "Net-(C6-Pad2)") (class "Default")
      (node (ref "C6") (pin "2") (pinfunction "2_2") (pintype "unspecified"))
      (node (ref "R4") (pin "2") (pinfunction "2_2") (pintype "unspecified"))
    )
    (net (code "65") (name "Net-(C25-Pad1)") (class "Default")
      (node (ref "C25") (pin "1") (pinfunction "1_1") (pintype "unspecified"))
      (node (ref "KEY1") (pin "1") (pinfunction "1_1") (pintype "unspecified"))
      (node (ref "KEY1") (pin "2") (pinfunction "2_2") (pintype "unspecified"))
      (node (ref "R41") (pin "2") (pinfunction "2_2") (pintype "unspecified"))
      (node (ref "R42") (pin "1") (pinfunction "1_1") (pintype "unspecified"))
    )
    (net (code "66") (name "Net-(CN1-Pad1)") (class "Default")
      (node (ref "CN1") (pin "1") (pinfunction "1_1") (pintype "unspecified"))
      (node (ref "R22") (pin "1") (pinfunction "1_1") (pintype "unspecified"))
      (node (ref "R25") (pin "2") (pinfunction "2_2") (pintype "unspecified"))
    )
    (net (code "67") (name "Net-(CN1-Pad2)") (class "Default")
      (node (ref "CN1") (pin "2") (pinfunction "2_2") (pintype "unspecified"))
      (node (ref "R21") (pin "1") (pinfunction "1_1") (pintype "unspecified"))
      (node (ref "R23") (pin "2") (pinfunction "2_2") (pintype "unspecified"))
    )
    (net (code "68") (name "Net-(CN1-Pad3)") (class "Default")
      (node (ref "CN1") (pin "3") (pinfunction "3_3") (pintype "unspecified"))
      (node (ref "R26") (pin "1") (pinfunction "1_1") (pintype "unspecified"))
      (node (ref "R28") (pin "2") (pinfunction "2_2") (pintype "unspecified"))
    )
    (net (code "69") (name "Net-(CN1-Pad4)") (class "Default")
      (node (ref "CN1") (pin "4") (pinfunction "4_4") (pintype "unspecified"))
      (node (ref "R27") (pin "1") (pinfunction "1_1") (pintype "unspecified"))
      (node (ref "R29") (pin "2") (pinfunction "2_2") (pintype "unspecified"))
    )
    (net (code "70") (name "Net-(D1-K)") (class "Default")
      (node (ref "D1") (pin "1") (pinfunction "K_1") (pintype "unspecified"))
      (node (ref "L1") (pin "2") (pinfunction "2_2") (pintype "unspecified"))
      (node (ref "R4") (pin "1") (pinfunction "1_1") (pintype "unspecified"))
      (node (ref "U1") (pin "3") (pinfunction "SW_3") (pintype "unspecified"))
    )
    (net (code "71") (name "Net-(LED4-Pad1)") (class "Default")
      (node (ref "LED4") (pin "1") (pinfunction "1_1") (pintype "unspecified"))
      (node (ref "R24") (pin "1") (pinfunction "1_1") (pintype "unspecified"))
    )
    (net (code "72") (name "Net-(M1-Pad1)") (class "Default")
      (node (ref "M1") (pin "1") (pinfunction "1_1") (pintype "unspecified"))
      (node (ref "U3") (pin "1") (pinfunction "AO1_1") (pintype "unspecified"))
      (node (ref "U3") (pin "2") (pinfunction "AO1_2") (pintype "unspecified"))
    )
    (net (code "73") (name "Net-(M1-Pad2)") (class "Default")
      (node (ref "M1") (pin "2") (pinfunction "2_2") (pintype "unspecified"))
      (node (ref "U3") (pin "5") (pinfunction "AO2_5") (pintype "unspecified"))
      (node (ref "U3") (pin "6") (pinfunction "AO2_6") (pintype "unspecified"))
    )
    (net (code "74") (name "Net-(M2-Pad1)") (class "Default")
      (node (ref "M2") (pin "1") (pinfunction "1_1") (pintype "unspecified"))
      (node (ref "U3") (pin "11") (pinfunction "BO1_11") (pintype "unspecified"))
      (node (ref "U3") (pin "12") (pinfunction "BO1_12") (pintype "unspecified"))
    )
    (net (code "75") (name "Net-(M2-Pad2)") (class "Default")
      (node (ref "M2") (pin "2") (pinfunction "2_2") (pintype "unspecified"))
      (node (ref "U3") (pin "7") (pinfunction "BO2_7") (pintype "unspecified"))
      (node (ref "U3") (pin "8") (pinfunction "BO2_8") (pintype "unspecified"))
    )
    (net (code "76") (name "Net-(R30-Pad2)") (class "Default")
      (node (ref "R30") (pin "2") (pinfunction "2_2") (pintype "unspecified"))
      (node (ref "U7") (pin "1") (pinfunction "1_1") (pintype "unspecified"))
    )
    (net (code "77") (name "Net-(R35-Pad2)") (class "Default")
      (node (ref "R35") (pin "2") (pinfunction "2_2") (pintype "unspecified"))
      (node (ref "U8") (pin "1") (pinfunction "1_1") (pintype "unspecified"))
    )
    (net (code "78") (name "Net-(R36-Pad2)") (class "Default")
      (node (ref "R36") (pin "2") (pinfunction "2_2") (pintype "unspecified"))
      (node (ref "U9") (pin "1") (pinfunction "1_1") (pintype "unspecified"))
    )
    (net (code "79") (name "Net-(R39-Pad2)") (class "Default")
      (node (ref "R39") (pin "2") (pinfunction "2_2") (pintype "unspecified"))
      (node (ref "U11") (pin "1") (pinfunction "1_1") (pintype "unspecified"))
    )
    (net (code "80") (name "Net-(U1-BS)") (class "Default")
      (node (ref "C6") (pin "1") (pinfunction "1_1") (pintype "unspecified"))
      (node (ref "U1") (pin "1") (pinfunction "BS_1") (pintype "unspecified"))
    )
    (net (code "81") (name "Net-(U1-COMP)") (class "Default")
      (node (ref "C4") (pin "2") (pinfunction "2_2") (pintype "unspecified"))
      (node (ref "C5") (pin "2") (pinfunction "2_2") (pintype "unspecified"))
      (node (ref "U1") (pin "6") (pinfunction "COMP_6") (pintype "unspecified"))
    )
    (net (code "82") (name "Net-(U1-FB)") (class "Default")
      (node (ref "R1") (pin "2") (pinfunction "2_2") (pintype "unspecified"))
      (node (ref "R2") (pin "2") (pinfunction "2_2") (pintype "unspecified"))
      (node (ref "U1") (pin "5") (pinfunction "FB_5") (pintype "unspecified"))
    )
    (net (code "83") (name "Net-(U1-SS)") (class "Default")
      (node (ref "C3") (pin "2") (pinfunction "2_2") (pintype "unspecified"))
      (node (ref "U1") (pin "8") (pinfunction "SS_8") (pintype "unspecified"))
    )
    (net (code "84") (name "Net-(U2-RXD)") (class "Default")
      (node (ref "R5") (pin "2") (pinfunction "2_2") (pintype "unspecified"))
      (node (ref "U2") (pin "3") (pinfunction "RXD_3") (pintype "unspecified"))
    )
    (net (code "85") (name "Net-(U2-TXD)") (class "Default")
      (node (ref "R7") (pin "2") (pinfunction "2_2") (pintype "unspecified"))
      (node (ref "U2") (pin "2") (pinfunction "TXD_2") (pintype "unspecified"))
    )
    (net (code "86") (name "Net-(U4-OSCI)") (class "Default")
      (node (ref "U4") (pin "1") (pinfunction "OSCI_1") (pintype "unspecified"))
      (node (ref "X2") (pin "2") (pinfunction "OSC2_2") (pintype "unspecified"))
    )
    (net (code "87") (name "Net-(U4-OSCO)") (class "Default")
      (node (ref "C14") (pin "2") (pinfunction "2_2") (pintype "unspecified"))
      (node (ref "U4") (pin "2") (pinfunction "OSCO_2") (pintype "unspecified"))
      (node (ref "X2") (pin "1") (pinfunction "OSC1_1") (pintype "unspecified"))
    )
    (net (code "88") (name "Net-(U4-VDD)") (class "Default")
      (node (ref "C15") (pin "1") (pinfunction "1_1") (pintype "unspecified"))
      (node (ref "D2") (pin "1") (pinfunction "1_1") (pintype "unspecified"))
      (node (ref "D3") (pin "1") (pinfunction "1_1") (pintype "unspecified"))
      (node (ref "U4") (pin "8") (pinfunction "VDD_8") (pintype "unspecified"))
    )
    (net (code "89") (name "Net-(U5-Q0)") (class "Default")
      (node (ref "R13") (pin "1") (pinfunction "1_1") (pintype "unspecified"))
      (node (ref "U5") (pin "19") (pinfunction "Q0_19") (pintype "unspecified"))
    )
    (net (code "90") (name "Net-(U5-Q1)") (class "Default")
      (node (ref "R14") (pin "1") (pinfunction "1_1") (pintype "unspecified"))
      (node (ref "U5") (pin "18") (pinfunction "Q1_18") (pintype "unspecified"))
    )
    (net (code "91") (name "Net-(U5-Q2)") (class "Default")
      (node (ref "R15") (pin "1") (pinfunction "1_1") (pintype "unspecified"))
      (node (ref "U5") (pin "17") (pinfunction "Q2_17") (pintype "unspecified"))
    )
    (net (code "92") (name "Net-(U5-Q3)") (class "Default")
      (node (ref "R16") (pin "1") (pinfunction "1_1") (pintype "unspecified"))
      (node (ref "U5") (pin "16") (pinfunction "Q3_16") (pintype "unspecified"))
    )
    (net (code "93") (name "Net-(U5-Q4)") (class "Default")
      (node (ref "R17") (pin "1") (pinfunction "1_1") (pintype "unspecified"))
      (node (ref "U5") (pin "15") (pinfunction "Q4_15") (pintype "unspecified"))
    )
    (net (code "94") (name "Net-(U5-Q5)") (class "Default")
      (node (ref "R18") (pin "1") (pinfunction "1_1") (pintype "unspecified"))
      (node (ref "U5") (pin "14") (pinfunction "Q5_14") (pintype "unspecified"))
    )
    (net (code "95") (name "Net-(U5-Q6)") (class "Default")
      (node (ref "R19") (pin "1") (pinfunction "1_1") (pintype "unspecified"))
      (node (ref "U5") (pin "13") (pinfunction "Q6_13") (pintype "unspecified"))
    )
    (net (code "96") (name "Net-(U5-Q7)") (class "Default")
      (node (ref "R20") (pin "1") (pinfunction "1_1") (pintype "unspecified"))
      (node (ref "U5") (pin "12") (pinfunction "Q7_12") (pintype "unspecified"))
    )
    (net (code "97") (name "Net-(U10-P1.0{slash}ADC0{slash}CCP1{slash}RXD2)") (class "Default")
      (node (ref "C21") (pin "1") (pinfunction "1_1") (pintype "unspecified"))
      (node (ref "R22") (pin "2") (pinfunction "2_2") (pintype "unspecified"))
      (node (ref "U10") (pin "4") (pinfunction "P1.0/ADC0/CCP1/RXD2_4") (pintype "unspecified"))
    )
    (net (code "98") (name "Net-(U10-P1.1{slash}ADC1{slash}CCP0{slash}TXD2)") (class "Default")
      (node (ref "C22") (pin "1") (pinfunction "1_1") (pintype "unspecified"))
      (node (ref "R21") (pin "2") (pinfunction "2_2") (pintype "unspecified"))
      (node (ref "U10") (pin "5") (pinfunction "P1.1/ADC1/CCP0/TXD2_5") (pintype "unspecified"))
    )
    (net (code "99") (name "Net-(U10-P1.2{slash}ADC2{slash}SS{slash}ECI)") (class "Default")
      (node (ref "C23") (pin "1") (pinfunction "1_1") (pintype "unspecified"))
      (node (ref "R26") (pin "2") (pinfunction "2_2") (pintype "unspecified"))
      (node (ref "U10") (pin "7") (pinfunction "P1.2/ADC2/SS/ECI_7") (pintype "unspecified"))
    )
    (net (code "100") (name "Net-(U10-P1.3{slash}ADC3{slash}MOSI)") (class "Default")
      (node (ref "C24") (pin "1") (pinfunction "1_1") (pintype "unspecified"))
      (node (ref "R27") (pin "2") (pinfunction "2_2") (pintype "unspecified"))
      (node (ref "U10") (pin "8") (pinfunction "P1.3/ADC3/MOSI_8") (pintype "unspecified"))
    )
    (net (code "101") (name "Net-(U10-P2.2{slash}MISO_2)") (class "Default")
      (node (ref "R6") (pin "1") (pinfunction "1_1") (pintype "unspecified"))
      (node (ref "U10") (pin "32") (pinfunction "P2.2/MISO_2_32") (pintype "bidirectional"))
    )
    (net (code "102") (name "Net-(U10-P2.3{slash}MOSI_2)") (class "Default")
      (node (ref "R8") (pin "1") (pinfunction "1_1") (pintype "unspecified"))
      (node (ref "U10") (pin "33") (pinfunction "P2.3/MOSI_2_33") (pintype "bidirectional"))
    )
    (net (code "103") (name "Net-(U10-P2.4{slash}ECI_3{slash}SS_2)") (class "Default")
      (node (ref "R9") (pin "1") (pinfunction "1_1") (pintype "unspecified"))
      (node (ref "U10") (pin "34") (pinfunction "P2.4/ECI_3/SS_2_34") (pintype "bidirectional"))
    )
    (net (code "104") (name "Net-(U10-P2.5{slash}CCP0_3)") (class "Default")
      (node (ref "R10") (pin "1") (pinfunction "1_1") (pintype "unspecified"))
      (node (ref "U10") (pin "35") (pinfunction "P2.5/CCP0_3_35") (pintype "bidirectional"))
    )
    (net (code "105") (name "Net-(U10-P2.6{slash}CCP1_3)") (class "Default")
      (node (ref "R11") (pin "1") (pinfunction "1_1") (pintype "unspecified"))
      (node (ref "U10") (pin "36") (pinfunction "P2.6/CCP1_3_36") (pintype "bidirectional"))
    )
    (net (code "106") (name "Net-(U10-P2.7{slash}CCP2_3)") (class "Default")
      (node (ref "R12") (pin "1") (pinfunction "1_1") (pintype "unspecified"))
      (node (ref "U10") (pin "37") (pinfunction "P2.7/CCP2_3_37") (pintype "bidirectional"))
    )
    (net (code "107") (name "Net-(USB1-VCC)") (class "Default")
      (node (ref "F1") (pin "1") (pinfunction "1_1") (pintype "unspecified"))
      (node (ref "USB1") (pin "1") (pinfunction "VCC_1") (pintype "unspecified"))
    )
    (net (code "108") (name "VUSB") (class "Default")
      (node (ref "C54") (pin "1") (pinfunction "1_1") (pintype "unspecified"))
      (node (ref "F1") (pin "2") (pinfunction "2_2") (pintype "unspecified"))
      (node (ref "U18") (pin "2") (pinfunction "VIN_2") (pintype "unspecified"))
    )
    (net (code "109") (name "unconnected-(C19-Pad1)") (class "Default")
      (node (ref "C19") (pin "1") (pinfunction "1_1") (pintype "unspecified"))
    )
    (net (code "110") (name "unconnected-(C19-Pad2)") (class "Default")
      (node (ref "C19") (pin "2") (pinfunction "2_2") (pintype "unspecified"))
    )
    (net (code "111") (name "unconnected-(C26-Pad1)") (class "Default")
      (node (ref "C26") (pin "1") (pinfunction "1_1") (pintype "unspecified"))
    )
    (net (code "112") (name "unconnected-(C26-Pad2)") (class "Default")
      (node (ref "C26") (pin "2") (pinfunction "2_2") (pintype "unspecified"))
    )
    (net (code "113") (name "unconnected-(CN3-Pad7)") (class "Default")
      (node (ref "CN3") (pin "7") (pinfunction "7_7") (pintype "unspecified+no_connect"))
    )
    (net (code "114") (name "unconnected-(U1-EN-Pad7)") (class "Default")
      (node (ref "U1") (pin "7") (pinfunction "EN_7") (pintype "unspecified+no_connect"))
    )
    (net (code "115") (name "unconnected-(U2-CTS#-Pad9)") (class "Default")
      (node (ref "U2") (pin "9") (pinfunction "CTS#_9") (pintype "unspecified+no_connect"))
    )
    (net (code "116") (name "unconnected-(U2-DCD#-Pad12)") (class "Default")
      (node (ref "U2") (pin "12") (pinfunction "DCD#_12") (pintype "unspecified+no_connect"))
    )
    (net (code "117") (name "unconnected-(U2-DSR#-Pad10)") (class "Default")
      (node (ref "U2") (pin "10") (pinfunction "DSR#_10") (pintype "unspecified+no_connect"))
    )
    (net (code "118") (name "unconnected-(U2-DTR#-Pad13)") (class "Default")
      (node (ref "U2") (pin "13") (pinfunction "DTR#_13") (pintype "unspecified+no_connect"))
    )
    (net (code "119") (name "unconnected-(U2-NC.-Pad7)") (class "Default")
      (node (ref "U2") (pin "7") (pinfunction "NC._7") (pintype "unspecified+no_connect"))
    )
    (net (code "120") (name "unconnected-(U2-NC.-Pad8)") (class "Default")
      (node (ref "U2") (pin "8") (pinfunction "NC._8") (pintype "unspecified+no_connect"))
    )
    (net (code "121") (name "unconnected-(U2-R232-Pad15)") (class "Default")
      (node (ref "U2") (pin "15") (pinfunction "R232_15") (pintype "unspecified+no_connect"))
    )
    (net (code "122") (name "unconnected-(U2-RI#-Pad11)") (class "Default")
      (node (ref "U2") (pin "11") (pinfunction "RI#_11") (pintype "unspecified+no_connect"))
    )
    (net (code "123") (name "unconnected-(U2-RTS#-Pad14)") (class "Default")
      (node (ref "U2") (pin "14") (pinfunction "RTS#_14") (pintype "unspecified+no_connect"))
    )
    (net (code "124") (name "unconnected-(U4-CLKOUT-Pad7)") (class "Default")
      (node (ref "U4") (pin "7") (pinfunction "CLKOUT_7") (pintype "unspecified+no_connect"))
    )
    (net (code "125") (name "unconnected-(U4-INT#-Pad3)") (class "Default")
      (node (ref "U4") (pin "3") (pinfunction "INT#_3") (pintype "unspecified+no_connect"))
    )
    (net (code "126") (name "unconnected-(U6-D0-Pad2)") (class "Default")
      (node (ref "U6") (pin "2") (pinfunction "D0_2") (pintype "unspecified"))
    )
    (net (code "127") (name "unconnected-(U6-D1-Pad3)") (class "Default")
      (node (ref "U6") (pin "3") (pinfunction "D1_3") (pintype "unspecified"))
    )
    (net (code "128") (name "unconnected-(U6-D2-Pad4)") (class "Default")
      (node (ref "U6") (pin "4") (pinfunction "D2_4") (pintype "unspecified"))
    )
    (net (code "129") (name "unconnected-(U6-D3-Pad5)") (class "Default")
      (node (ref "U6") (pin "5") (pinfunction "D3_5") (pintype "unspecified"))
    )
    (net (code "130") (name "unconnected-(U6-D4-Pad6)") (class "Default")
      (node (ref "U6") (pin "6") (pinfunction "D4_6") (pintype "unspecified"))
    )
    (net (code "131") (name "unconnected-(U6-D5-Pad7)") (class "Default")
      (node (ref "U6") (pin "7") (pinfunction "D5_7") (pintype "unspecified"))
    )
    (net (code "132") (name "unconnected-(U6-D6-Pad8)") (class "Default")
      (node (ref "U6") (pin "8") (pinfunction "D6_8") (pintype "unspecified"))
    )
    (net (code "133") (name "unconnected-(U6-D7-Pad9)") (class "Default")
      (node (ref "U6") (pin "9") (pinfunction "D7_9") (pintype "unspecified"))
    )
    (net (code "134") (name "unconnected-(U6-GND-Pad10)") (class "Default")
      (node (ref "U6") (pin "10") (pinfunction "GND_10") (pintype "unspecified"))
    )
    (net (code "135") (name "unconnected-(U6-LE-Pad11)") (class "Default")
      (node (ref "U6") (pin "11") (pinfunction "LE_11") (pintype "unspecified"))
    )
    (net (code "136") (name "unconnected-(U6-OE-Pad1)") (class "Default")
      (node (ref "U6") (pin "1") (pinfunction "OE_1") (pintype "unspecified"))
    )
    (net (code "137") (name "unconnected-(U6-Q0-Pad19)") (class "Default")
      (node (ref "U6") (pin "19") (pinfunction "Q0_19") (pintype "unspecified"))
    )
    (net (code "138") (name "unconnected-(U6-Q1-Pad18)") (class "Default")
      (node (ref "U6") (pin "18") (pinfunction "Q1_18") (pintype "unspecified"))
    )
    (net (code "139") (name "unconnected-(U6-Q2-Pad17)") (class "Default")
      (node (ref "U6") (pin "17") (pinfunction "Q2_17") (pintype "unspecified"))
    )
    (net (code "140") (name "unconnected-(U6-Q3-Pad16)") (class "Default")
      (node (ref "U6") (pin "16") (pinfunction "Q3_16") (pintype "unspecified"))
    )
    (net (code "141") (name "unconnected-(U6-Q4-Pad15)") (class "Default")
      (node (ref "U6") (pin "15") (pinfunction "Q4_15") (pintype "unspecified"))
    )
    (net (code "142") (name "unconnected-(U6-Q5-Pad14)") (class "Default")
      (node (ref "U6") (pin "14") (pinfunction "Q5_14") (pintype "unspecified"))
    )
    (net (code "143") (name "unconnected-(U6-Q6-Pad13)") (class "Default")
      (node (ref "U6") (pin "13") (pinfunction "Q6_13") (pintype "unspecified"))
    )
    (net (code "144") (name "unconnected-(U6-Q7-Pad12)") (class "Default")
      (node (ref "U6") (pin "12") (pinfunction "Q7_12") (pintype "unspecified"))
    )
    (net (code "145") (name "unconnected-(U6-VCC-Pad20)") (class "Default")
      (node (ref "U6") (pin "20") (pinfunction "VCC_20") (pintype "unspecified"))
    )
    (net (code "146") (name "unconnected-(U10-P1.6{slash}ADC6{slash}RXD_3{slash}XTAL2-Pad11)") (class "Default")
      (node (ref "U10") (pin "11") (pinfunction "P1.6/ADC6/RXD_3/XTAL2_11") (pintype "bidirectional+no_connect"))
    )
    (net (code "147") (name "unconnected-(U10-P1.7{slash}ADC7{slash}TXD_3{slash}XTAL1-Pad12)") (class "Default")
      (node (ref "U10") (pin "12") (pinfunction "P1.7/ADC7/TXD_3/XTAL1_12") (pintype "bidirectional+no_connect"))
    )
    (net (code "148") (name "unconnected-(U10-P5.4{slash}RST{slash}MCLK0{slash}SS_3-Pad13)") (class "Default")
      (node (ref "U10") (pin "13") (pinfunction "P5.4/RST/MCLK0/SS_3_13") (pintype "unspecified+no_connect"))
    )
  )
)
